# I2C_Interface.net
KiCad netlist of a schematic drawn in Altium Designer
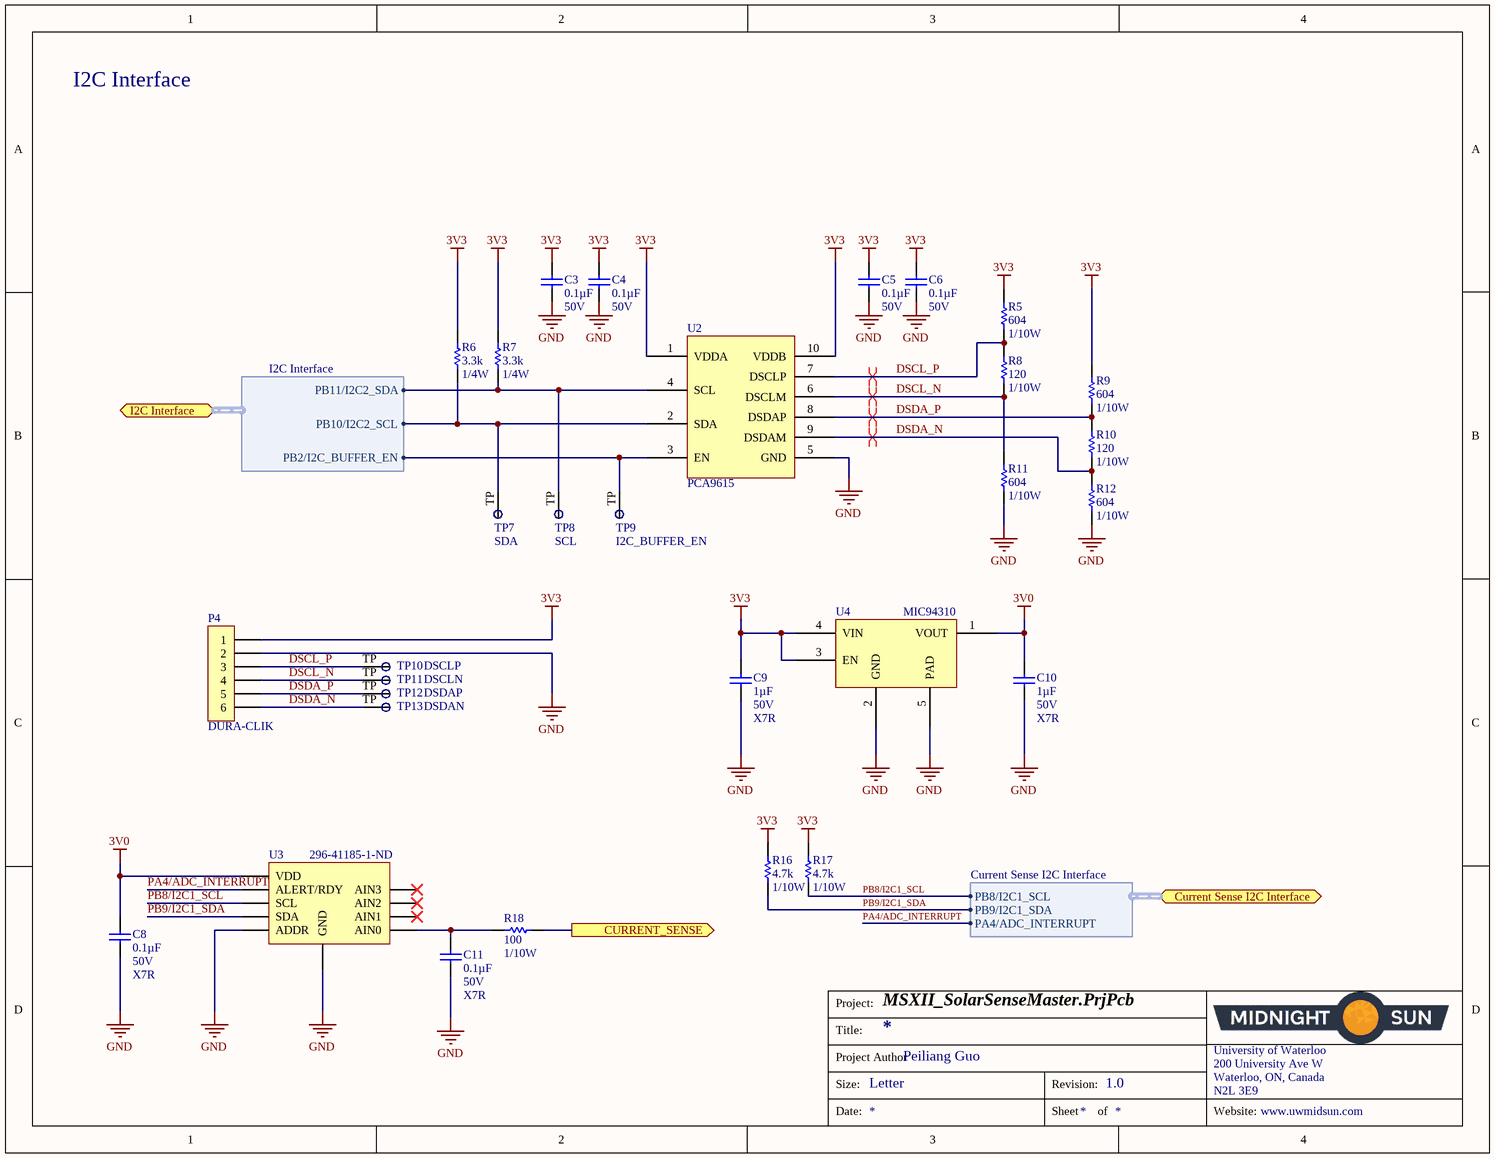
[diagram p0: I2C_Interface.SchDoc]

(export (version "E")
  (design (tool "Eeschema 10.0.6"))
  (components
    (comp (ref "C3")
      (value "CAP CER 0.1UF 50V 10% X7R 0603")
      (footprint "CAP, 0603")
      (description "0.10µF ±10% 50V Ceramic Capacitor X7R 0603 (1608 Metric)")
      (fields
        (field (name "TOLERANCE") "±10%")
        (field (name "CAPACITANCE") "0.1µF")
        (field (name "VOLTAGE") "50V")
      )
      (libsource (lib "Schematic Diagrams") (part "CAP CER 0.1UF 50V 10% X7R 0603"))
    )
    (comp (ref "C4")
      (value "CAP CER 0.1UF 50V 10% X7R 0603")
      (footprint "CAP, 0603")
      (description "0.10µF ±10% 50V Ceramic Capacitor X7R 0603 (1608 Metric)")
      (fields
        (field (name "TOLERANCE") "±10%")
        (field (name "CAPACITANCE") "0.1µF")
        (field (name "VOLTAGE") "50V")
      )
      (libsource (lib "Schematic Diagrams") (part "CAP CER 0.1UF 50V 10% X7R 0603"))
    )
    (comp (ref "C5")
      (value "CAP CER 0.1UF 50V 10% X7R 0603")
      (footprint "CAP, 0603")
      (description "0.10µF ±10% 50V Ceramic Capacitor X7R 0603 (1608 Metric)")
      (fields
        (field (name "TOLERANCE") "±10%")
        (field (name "CAPACITANCE") "0.1µF")
        (field (name "VOLTAGE") "50V")
      )
      (libsource (lib "Schematic Diagrams") (part "CAP CER 0.1UF 50V 10% X7R 0603"))
    )
    (comp (ref "C6")
      (value "CAP CER 0.1UF 50V 10% X7R 0603")
      (footprint "CAP, 0603")
      (description "0.10µF ±10% 50V Ceramic Capacitor X7R 0603 (1608 Metric)")
      (fields
        (field (name "TOLERANCE") "±10%")
        (field (name "CAPACITANCE") "0.1µF")
        (field (name "VOLTAGE") "50V")
      )
      (libsource (lib "Schematic Diagrams") (part "CAP CER 0.1UF 50V 10% X7R 0603"))
    )
    (comp (ref "C8")
      (value "CAP CER 0.1UF 50V 10% X7R 0603")
      (footprint "CAP, 0603")
      (description "0.10µF ±10% 50V Ceramic Capacitor X7R 0603 (1608 Metric)")
      (fields
        (field (name "TOLERANCE") "±10%")
        (field (name "CAPACITANCE") "0.1µF")
        (field (name "VOLTAGE") "50V")
        (field (name "TEMPERATURE COEFFICIENT") "X7R")
      )
      (libsource (lib "Schematic Diagrams") (part "CAP CER 0.1UF 50V 10% X7R 0603"))
    )
    (comp (ref "C9")
      (value "CAP CER 1UF 50V 10% X7R 0603")
      (footprint "CAP, 0603")
      (description "1µF ±10% 50V Ceramic Capacitor X7R 0603 (1608 Metric)")
      (fields
        (field (name "TOLERANCE") "±10%")
        (field (name "CAPACITANCE") "1µF")
        (field (name "VOLTAGE") "50V")
        (field (name "TEMPERATURE COEFFICIENT") "X7R")
      )
      (libsource (lib "Schematic Diagrams") (part "CAP CER 1UF 50V 10% X7R 0603"))
    )
    (comp (ref "C10")
      (value "CAP CER 1UF 50V 10% X7R 0603")
      (footprint "CAP, 0603")
      (description "1µF ±10% 50V Ceramic Capacitor X7R 0603 (1608 Metric)")
      (fields
        (field (name "TOLERANCE") "±10%")
        (field (name "CAPACITANCE") "1µF")
        (field (name "VOLTAGE") "50V")
        (field (name "TEMPERATURE COEFFICIENT") "X7R")
      )
      (libsource (lib "Schematic Diagrams") (part "CAP CER 1UF 50V 10% X7R 0603"))
    )
    (comp (ref "C11")
      (value "CAP CER 0.1UF 50V 10% X7R 0603")
      (footprint "CAP, 0603")
      (description "0.10µF ±10% 50V Ceramic Capacitor X7R 0603 (1608 Metric)")
      (fields
        (field (name "TOLERANCE") "±10%")
        (field (name "CAPACITANCE") "0.1µF")
        (field (name "VOLTAGE") "50V")
        (field (name "TEMPERATURE COEFFICIENT") "X7R")
      )
      (libsource (lib "Schematic Diagrams") (part "CAP CER 0.1UF 50V 10% X7R 0603"))
    )
    (comp (ref "P4")
      (value "DURA-CLIK")
      (footprint "CONN, 6POS DURA-CLIK VERT")
      (description "6 Positions Header, Shrouded Connector 0.079\" (2.00mm) Surface Mount, Vertical Tin")
      (fields (field (name "MANUFACTURER") "Molex") (field (name "MANUFACTURER PART NUMBER") "5600200820"))
      (libsource (lib "Schematic Diagrams") (part "CONN 6POS DURA-CLIK 0.079{dblquote}"))
    )
    (comp (ref "R5")
      (value "RES 604 OHM 1% 1/10W 0603")
      (footprint "RES, 0603")
      (description "RES SMD 604 OHM 1% 1/10W 0603")
      (fields
        (field (name "TOLERANCE") "±1%")
        (field (name "RESISTANCE") "604")
        (field (name "POWER") "1/10W")
      )
      (libsource (lib "Schematic Diagrams") (part "RES 604 OHM 1% 1/10W 0603"))
    )
    (comp (ref "R6")
      (value "RES 3.3K OHM 1% 1/4W 0603")
      (footprint "RES, 0603")
      (fields
        (field (name "TOLERANCE") "±1%")
        (field (name "RESISTANCE") "3.3k")
        (field (name "POWER") "1/4W")
      )
      (libsource (lib "Schematic Diagrams") (part "RES 3.3K OHM 1% 1/4W 0603"))
    )
    (comp (ref "R7")
      (value "RES 3.3K OHM 1% 1/4W 0603")
      (footprint "RES, 0603")
      (fields
        (field (name "TOLERANCE") "±1%")
        (field (name "RESISTANCE") "3.3k")
        (field (name "POWER") "1/4W")
      )
      (libsource (lib "Schematic Diagrams") (part "RES 3.3K OHM 1% 1/4W 0603"))
    )
    (comp (ref "R8")
      (value "RES 120 OHM 1% 1/10W 0603")
      (footprint "RES, 0603")
      (description "RES SMD 120 OHM 1% 1/10W 0603")
      (fields
        (field (name "TOLERANCE") "±1%")
        (field (name "RESISTANCE") "120")
        (field (name "POWER") "1/10W")
      )
      (libsource (lib "Schematic Diagrams") (part "RES 120 OHM 1% 1/10W 0603"))
    )
    (comp (ref "R9")
      (value "RES 604 OHM 1% 1/10W 0603")
      (footprint "RES, 0603")
      (description "RES SMD 604 OHM 1% 1/10W 0603")
      (fields
        (field (name "TOLERANCE") "±1%")
        (field (name "RESISTANCE") "604")
        (field (name "POWER") "1/10W")
      )
      (libsource (lib "Schematic Diagrams") (part "RES 604 OHM 1% 1/10W 0603"))
    )
    (comp (ref "R10")
      (value "RES 120 OHM 1% 1/10W 0603")
      (footprint "RES, 0603")
      (description "RES SMD 120 OHM 1% 1/10W 0603")
      (fields
        (field (name "TOLERANCE") "±1%")
        (field (name "RESISTANCE") "120")
        (field (name "POWER") "1/10W")
      )
      (libsource (lib "Schematic Diagrams") (part "RES 120 OHM 1% 1/10W 0603"))
    )
    (comp (ref "R11")
      (value "RES 604 OHM 1% 1/10W 0603")
      (footprint "RES, 0603")
      (description "RES SMD 604 OHM 1% 1/10W 0603")
      (fields
        (field (name "TOLERANCE") "±1%")
        (field (name "RESISTANCE") "604")
        (field (name "POWER") "1/10W")
      )
      (libsource (lib "Schematic Diagrams") (part "RES 604 OHM 1% 1/10W 0603"))
    )
    (comp (ref "R12")
      (value "RES 604 OHM 1% 1/10W 0603")
      (footprint "RES, 0603")
      (description "RES SMD 604 OHM 1% 1/10W 0603")
      (fields
        (field (name "TOLERANCE") "±1%")
        (field (name "RESISTANCE") "604")
        (field (name "POWER") "1/10W")
      )
      (libsource (lib "Schematic Diagrams") (part "RES 604 OHM 1% 1/10W 0603"))
    )
    (comp (ref "R16")
      (value "RES 4.7K OHM 1% 1/10W 0603")
      (footprint "RES, 0603")
      (description "4.7k Ohm ±1% 0.1W, 1/10W Chip Resistor 0603 (1608 Metric) Moisture Resistant Thick Film")
      (fields
        (field (name "TOLERANCE") "±1%")
        (field (name "RESISTANCE (OHMS)") "4.7k")
        (field (name "POWER (WATTS)") "1/10W")
      )
      (libsource (lib "Schematic Diagrams") (part "RES 4.7K OHM 1% 1/10W 0603"))
    )
    (comp (ref "R17")
      (value "RES 4.7K OHM 1% 1/10W 0603")
      (footprint "RES, 0603")
      (description "4.7k Ohm ±1% 0.1W, 1/10W Chip Resistor 0603 (1608 Metric) Moisture Resistant Thick Film")
      (fields
        (field (name "TOLERANCE") "±1%")
        (field (name "RESISTANCE (OHMS)") "4.7k")
        (field (name "POWER (WATTS)") "1/10W")
      )
      (libsource (lib "Schematic Diagrams") (part "RES 4.7K OHM 1% 1/10W 0603"))
    )
    (comp (ref "R18")
      (value "RES 100 OHM 1% 1/10W 0603")
      (footprint "RES, 0603")
      (description "100 Ohm ±1% 0.1W, 1/10W Chip Resistor 0603 (1608 Metric) Moisture Resistant Thick Film")
      (fields
        (field (name "TOLERANCE") "±1%")
        (field (name "RESISTANCE") "100")
        (field (name "POWER") "1/10W")
      )
      (libsource (lib "Schematic Diagrams") (part "RES 100 OHM 1% 1/10W 0603"))
    )
    (comp (ref "TP7")
      (value "SDA")
      (footprint "Test Point")
      (libsource (lib "Schematic Diagrams") (part "Test Point"))
    )
    (comp (ref "TP8")
      (value "SCL")
      (footprint "Test Point")
      (libsource (lib "Schematic Diagrams") (part "Test Point"))
    )
    (comp (ref "TP9")
      (value "I2C_BUFFER_EN")
      (footprint "Test Point")
      (libsource (lib "Schematic Diagrams") (part "Test Point"))
    )
    (comp (ref "TP10")
      (value "DSCLP")
      (footprint "Test Point")
      (libsource (lib "Schematic Diagrams") (part "Test Point"))
    )
    (comp (ref "TP11")
      (value "DSCLN")
      (footprint "Test Point")
      (libsource (lib "Schematic Diagrams") (part "Test Point"))
    )
    (comp (ref "TP12")
      (value "DSDAP")
      (footprint "Test Point")
      (libsource (lib "Schematic Diagrams") (part "Test Point"))
    )
    (comp (ref "TP13")
      (value "DSDAN")
      (footprint "Test Point")
      (libsource (lib "Schematic Diagrams") (part "Test Point"))
    )
    (comp (ref "U2")
      (value "IC DIFFERENTIAL I2C BUFFER PCA9615")
      (footprint "TSSOP50P490X110-10N")
      (description "Buffer, ReDriver 2 Channel 400kHz 10-TSSOP")
      (fields
        (field (name "MANUFACTURER") "NXP USA Inc.")
        (field (name "MANUFACTURER PART NUMBER") "PCA9615DPJ")
        (field (name "BASE PART NUMBER") "PCA9615")
      )
      (libsource (lib "Schematic Diagrams") (part "IC DIFFERENTIAL I2C BUFFER PCA9615"))
    )
    (comp (ref "U3")
      (value "Quad ADC")
      (footprint "IC ADC VSSOP10")
      (description "12 Bit Analog to Digital Converter 4 Input 1 Sigma-Delta 10-VSSOP")
      (fields
        (field (name "MANUFACTURER") "Texas Instruments")
        (field (name "MANUFACTURER PART NUMBER") "ADS1015IDGSR")
        (field (name "SUPPLIER PART NUMBER 1") "296-41185-1-ND")
      )
      (libsource (lib "Schematic Diagrams") (part "IC ADC 12-BIT VSSOP-10"))
    )
    (comp (ref "U4")
      (value "MIC94310")
      (footprint "IC REG LDO 3V 0.2A 4-TDFN")
      (fields
        (field (name "MANUFACTURER") "Microchip Technology")
        (field (name "MANUFACTURER PART NUMBER") "MIC94310-PYMT-TR")
      )
      (libsource (lib "Schematic Diagrams") (part "IC REG LDO 3V 0.2A 4-TDFN"))
    )
  )
  (nets
    (net (code "5") (name "/CURRENT_SENSE") (class "Default")
      (node (ref "R18") (pin "1") (pinfunction "1_1") (pintype "passive"))
    )
    (net (code "6") (name "/DSCL_N") (class "Default")
      (node (ref "P4") (pin "4") (pinfunction "4_4") (pintype "passive"))
      (node (ref "R11") (pin "1") (pinfunction "1_1") (pintype "passive"))
      (node (ref "R8") (pin "2") (pinfunction "2_2") (pintype "passive"))
      (node (ref "TP11") (pin "TP") (pinfunction "1_TP") (pintype "passive"))
      (node (ref "U2") (pin "6") (pinfunction "DSCLM_6") (pintype "passive"))
    )
    (net (code "7") (name "/DSCL_P") (class "Default")
      (node (ref "P4") (pin "3") (pinfunction "3_3") (pintype "passive"))
      (node (ref "R5") (pin "2") (pinfunction "2_2") (pintype "passive"))
      (node (ref "R8") (pin "1") (pinfunction "1_1") (pintype "passive"))
      (node (ref "TP10") (pin "TP") (pinfunction "1_TP") (pintype "passive"))
      (node (ref "U2") (pin "7") (pinfunction "DSCLP_7") (pintype "passive"))
    )
    (net (code "8") (name "/DSDA_N") (class "Default")
      (node (ref "P4") (pin "6") (pinfunction "6_6") (pintype "passive"))
      (node (ref "R10") (pin "2") (pinfunction "2_2") (pintype "passive"))
      (node (ref "R12") (pin "1") (pinfunction "1_1") (pintype "passive"))
      (node (ref "TP13") (pin "TP") (pinfunction "1_TP") (pintype "passive"))
      (node (ref "U2") (pin "9") (pinfunction "DSDAM_9") (pintype "passive"))
    )
    (net (code "9") (name "/DSDA_P") (class "Default")
      (node (ref "P4") (pin "5") (pinfunction "5_5") (pintype "passive"))
      (node (ref "R10") (pin "1") (pinfunction "1_1") (pintype "passive"))
      (node (ref "R9") (pin "2") (pinfunction "2_2") (pintype "passive"))
      (node (ref "TP12") (pin "TP") (pinfunction "1_TP") (pintype "passive"))
      (node (ref "U2") (pin "8") (pinfunction "DSDAP_8") (pintype "passive"))
    )
    (net (code "10") (name "/PA4{slash}ADC_INTERRUPT") (class "Default")
      (node (ref "U3") (pin "2") (pinfunction "ALERT/RDY_2") (pintype "passive"))
    )
    (net (code "11") (name "/PB8{slash}I2C1_SCL") (class "Default")
      (node (ref "R17") (pin "2") (pinfunction "2_2") (pintype "passive"))
      (node (ref "U3") (pin "10") (pinfunction "SCL_10") (pintype "passive"))
    )
    (net (code "12") (name "/PB9{slash}I2C1_SDA") (class "Default")
      (node (ref "R16") (pin "2") (pinfunction "2_2") (pintype "passive"))
      (node (ref "U3") (pin "9") (pinfunction "SDA_9") (pintype "passive"))
    )
    (net (code "15") (name "3V0") (class "Default")
      (node (ref "C10") (pin "1") (pinfunction "1_1") (pintype "passive"))
      (node (ref "C8") (pin "1") (pinfunction "1_1") (pintype "passive"))
      (node (ref "U3") (pin "8") (pinfunction "VDD_8") (pintype "passive"))
      (node (ref "U4") (pin "1") (pinfunction "VOUT_1") (pintype "passive"))
    )
    (net (code "16") (name "3V3") (class "Default")
      (node (ref "C3") (pin "1") (pinfunction "1_1") (pintype "passive"))
      (node (ref "C4") (pin "1") (pinfunction "1_1") (pintype "passive"))
      (node (ref "C5") (pin "1") (pinfunction "1_1") (pintype "passive"))
      (node (ref "C6") (pin "1") (pinfunction "1_1") (pintype "passive"))
      (node (ref "C9") (pin "1") (pinfunction "1_1") (pintype "passive"))
      (node (ref "P4") (pin "1") (pinfunction "1_1") (pintype "passive"))
      (node (ref "R16") (pin "1") (pinfunction "1_1") (pintype "passive"))
      (node (ref "R17") (pin "1") (pinfunction "1_1") (pintype "passive"))
      (node (ref "R5") (pin "1") (pinfunction "1_1") (pintype "passive"))
      (node (ref "R6") (pin "1") (pinfunction "1_1") (pintype "passive"))
      (node (ref "R7") (pin "1") (pinfunction "1_1") (pintype "passive"))
      (node (ref "R9") (pin "1") (pinfunction "1_1") (pintype "passive"))
      (node (ref "U2") (pin "1") (pinfunction "VDDA_1") (pintype "passive"))
      (node (ref "U2") (pin "10") (pinfunction "VDDB_10") (pintype "passive"))
      (node (ref "U4") (pin "3") (pinfunction "EN_3") (pintype "passive"))
      (node (ref "U4") (pin "4") (pinfunction "VIN_4") (pintype "passive"))
    )
    (net (code "17") (name "GND") (class "Default")
      (node (ref "C10") (pin "2") (pinfunction "2_2") (pintype "passive"))
      (node (ref "C11") (pin "2") (pinfunction "2_2") (pintype "passive"))
      (node (ref "C3") (pin "2") (pinfunction "2_2") (pintype "passive"))
      (node (ref "C4") (pin "2") (pinfunction "2_2") (pintype "passive"))
      (node (ref "C5") (pin "2") (pinfunction "2_2") (pintype "passive"))
      (node (ref "C6") (pin "2") (pinfunction "2_2") (pintype "passive"))
      (node (ref "C8") (pin "2") (pinfunction "2_2") (pintype "passive"))
      (node (ref "C9") (pin "2") (pinfunction "2_2") (pintype "passive"))
      (node (ref "P4") (pin "2") (pinfunction "2_2") (pintype "passive"))
      (node (ref "R11") (pin "2") (pinfunction "2_2") (pintype "passive"))
      (node (ref "R12") (pin "2") (pinfunction "2_2") (pintype "passive"))
      (node (ref "U2") (pin "5") (pinfunction "GND_5") (pintype "passive"))
      (node (ref "U3") (pin "1") (pinfunction "ADDR_1") (pintype "passive"))
      (node (ref "U3") (pin "3") (pinfunction "GND_3") (pintype "passive"))
      (node (ref "U4") (pin "2") (pinfunction "GND_2") (pintype "passive"))
      (node (ref "U4") (pin "5") (pinfunction "PAD_5") (pintype "passive"))
    )
    (net (code "18") (name "Net-(TP7-1)") (class "Default")
      (node (ref "R6") (pin "2") (pinfunction "2_2") (pintype "passive"))
      (node (ref "TP7") (pin "TP") (pinfunction "1_TP") (pintype "passive"))
      (node (ref "U2") (pin "2") (pinfunction "SDA_2") (pintype "passive"))
    )
    (net (code "19") (name "Net-(TP8-1)") (class "Default")
      (node (ref "R7") (pin "2") (pinfunction "2_2") (pintype "passive"))
      (node (ref "TP8") (pin "TP") (pinfunction "1_TP") (pintype "passive"))
      (node (ref "U2") (pin "4") (pinfunction "SCL_4") (pintype "passive"))
    )
    (net (code "20") (name "Net-(TP9-1)") (class "Default")
      (node (ref "TP9") (pin "TP") (pinfunction "1_TP") (pintype "passive"))
      (node (ref "U2") (pin "3") (pinfunction "EN_3") (pintype "passive"))
    )
    (net (code "21") (name "Net-(U3-AIN0)") (class "Default")
      (node (ref "C11") (pin "1") (pinfunction "1_1") (pintype "passive"))
      (node (ref "R18") (pin "2") (pinfunction "2_2") (pintype "passive"))
      (node (ref "U3") (pin "4") (pinfunction "AIN0_4") (pintype "passive"))
    )
    (net (code "22") (name "unconnected-(U3-AIN1-Pad5)") (class "Default")
      (node (ref "U3") (pin "5") (pinfunction "AIN1_5") (pintype "passive+no_connect"))
    )
    (net (code "23") (name "unconnected-(U3-AIN2-Pad6)") (class "Default")
      (node (ref "U3") (pin "6") (pinfunction "AIN2_6") (pintype "passive+no_connect"))
    )
    (net (code "24") (name "unconnected-(U3-AIN3-Pad7)") (class "Default")
      (node (ref "U3") (pin "7") (pinfunction "AIN3_7") (pintype "passive+no_connect"))
    )
  )
)
